# ControlBoard.net
KiCad netlist of a schematic drawn in EAGLE
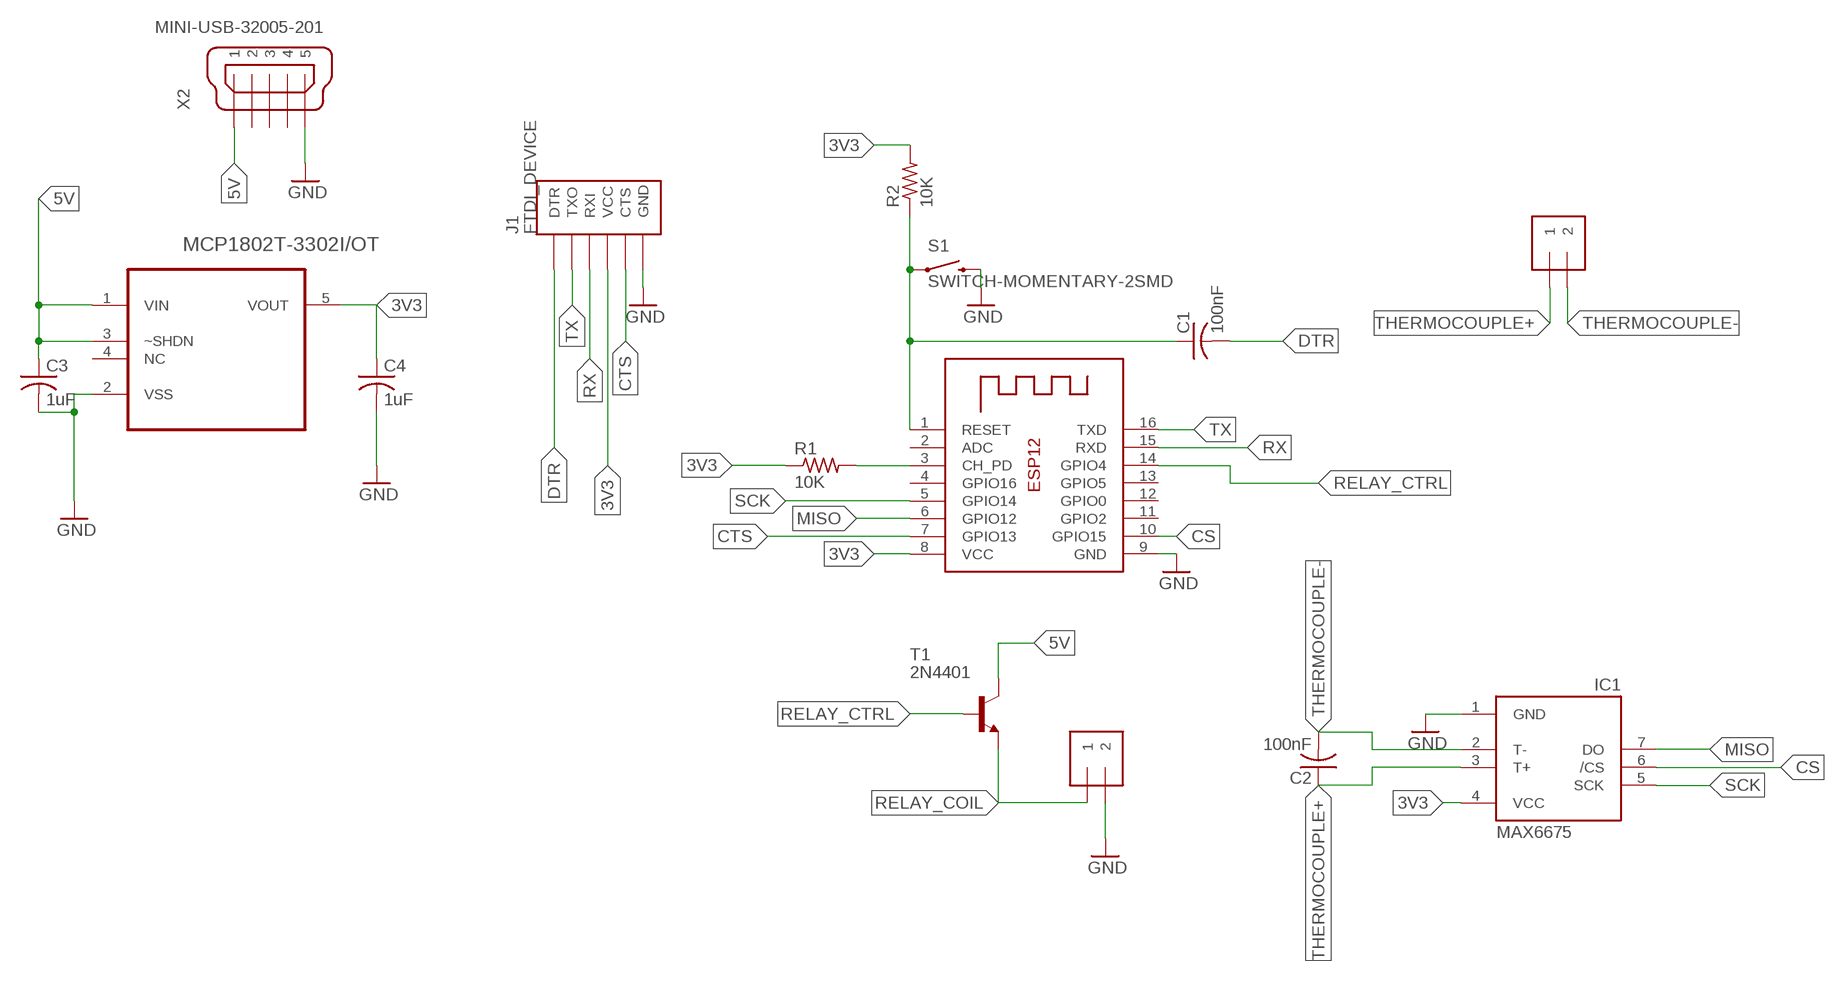
[diagram p0: schematic, sheet 1]

(export (version "E")
  (design (tool "Eeschema 10.0.6"))
  (components
    (comp (ref "C1")
      (value "100nF")
      (footprint "eagle-import:C0603")
      (libsource (lib "eagle-import") (part "C-USC0603"))
    )
    (comp (ref "C2")
      (value "100nF")
      (footprint "eagle-import:C0603")
      (libsource (lib "eagle-import") (part "C-USC0603"))
    )
    (comp (ref "C3")
      (value "1uF")
      (footprint "eagle-import:C0603")
      (libsource (lib "eagle-import") (part "C-USC0603"))
    )
    (comp (ref "C4")
      (value "1uF")
      (footprint "eagle-import:C0603")
      (libsource (lib "eagle-import") (part "C-USC0603"))
    )
    (comp (ref "IC1")
      (value "MAX6675")
      (footprint "eagle-import:SO08")
      (libsource (lib "eagle-import") (part "MAX6675"))
    )
    (comp (ref "J1")
      (value "FTDI_DEVICE")
      (footprint "eagle-import:FTDI_DEVICE_SIDE")
      (libsource (lib "eagle-import") (part "FTDI_DEVICE"))
    )
    (comp (ref "J2")
      (value "1X2-3.5MM")
      (footprint "eagle-import:1X2-3.5MM")
      (libsource (lib "eagle-import") (part "1X2-3.5MM"))
    )
    (comp (ref "J3")
      (value "1X2-3.5MM")
      (footprint "eagle-import:1X2-3.5MM")
      (libsource (lib "eagle-import") (part "1X2-3.5MM"))
    )
    (comp (ref "MCP1802T-3302I/OT")
      (value "MCP1802T-3002I/OT")
      (footprint "eagle-import:SOT95P270X145-5N")
      (libsource (lib "eagle-import") (part "MCP1802T-3002I/OT"))
    )
    (comp (ref "R1")
      (value "10K")
      (footprint "eagle-import:R0603")
      (libsource (lib "eagle-import") (part "R-US_R0603"))
    )
    (comp (ref "R2")
      (value "10K")
      (footprint "eagle-import:R0603")
      (libsource (lib "eagle-import") (part "R-US_R0603"))
    )
    (comp (ref "S1")
      (value "SWITCH-MOMENTARY-2SMD")
      (footprint "eagle-import:TACTILE-SWITCH-SMD")
      (libsource (lib "eagle-import") (part "SWITCH-MOMENTARY-2SMD"))
    )
    (comp (ref "T1")
      (value "2N4401")
      (footprint "eagle-import:TO92-EBC")
      (libsource (lib "eagle-import") (part "-NPN-TO92-EBC"))
    )
    (comp (ref "X1")
      (value "ESP-12")
      (footprint "eagle-import:ESP-12")
      (libsource (lib "eagle-import") (part "ESP-12"))
    )
    (comp (ref "X2")
      (value "MINI-USB-32005-201")
      (footprint "eagle-import:32005-201")
      (libsource (lib "eagle-import") (part "MINI-USB-32005-201"))
    )
  )
  (nets
    (net (code "1") (name "3V3") (class "Default")
      (node (ref "C4") (pin "1") (pinfunction "1_1") (pintype "passive"))
      (node (ref "IC1") (pin "4") (pinfunction "VCC_4") (pintype "power_in"))
      (node (ref "J1") (pin "P$4") (pinfunction "VCC_P$4") (pintype "bidirectional"))
      (node (ref "MCP1802T-3302I/OT") (pin "5") (pinfunction "VOUT_5") (pintype "output"))
      (node (ref "R1") (pin "1") (pinfunction "1_1") (pintype "passive"))
      (node (ref "R2") (pin "2") (pinfunction "2_2") (pintype "passive"))
      (node (ref "X1") (pin "8") (pinfunction "VCC_8") (pintype "power_in"))
    )
    (net (code "2") (name "5V") (class "Default")
      (node (ref "C3") (pin "1") (pinfunction "1_1") (pintype "passive"))
      (node (ref "MCP1802T-3302I/OT") (pin "1") (pinfunction "VIN_1") (pintype "power_in"))
      (node (ref "MCP1802T-3302I/OT") (pin "3") (pinfunction "~{SHDN}_3") (pintype "input"))
      (node (ref "T1") (pin "C") (pinfunction "C_C") (pintype "passive"))
      (node (ref "X2") (pin "1") (pinfunction "1_1") (pintype "passive"))
    )
    (net (code "3") (name "CS") (class "Default")
      (node (ref "IC1") (pin "6") (pinfunction "/CS_6") (pintype "input"))
      (node (ref "X1") (pin "10") (pinfunction "GPIO15_10") (pintype "bidirectional"))
    )
    (net (code "4") (name "CTS") (class "Default")
      (node (ref "J1") (pin "P$5") (pinfunction "CTS_P$5") (pintype "bidirectional"))
      (node (ref "X1") (pin "7") (pinfunction "GPIO13_7") (pintype "bidirectional"))
    )
    (net (code "5") (name "DTR") (class "Default")
      (node (ref "C1") (pin "2") (pinfunction "2_2") (pintype "passive"))
      (node (ref "J1") (pin "P$1") (pinfunction "DTR_P$1") (pintype "bidirectional"))
    )
    (net (code "6") (name "GND") (class "Default")
      (node (ref "C3") (pin "2") (pinfunction "2_2") (pintype "passive"))
      (node (ref "C4") (pin "2") (pinfunction "2_2") (pintype "passive"))
      (node (ref "IC1") (pin "1") (pinfunction "GND_1") (pintype "power_in"))
      (node (ref "J1") (pin "P$6") (pinfunction "GND_P$6") (pintype "bidirectional"))
      (node (ref "J3") (pin "2") (pinfunction "2_2") (pintype "passive"))
      (node (ref "MCP1802T-3302I/OT") (pin "2") (pinfunction "VSS_2") (pintype "passive"))
      (node (ref "S1") (pin "3") (pinfunction "2_3") (pintype "passive"))
      (node (ref "X1") (pin "9") (pinfunction "GND_9") (pintype "power_in"))
      (node (ref "X2") (pin "5") (pinfunction "5_5") (pintype "passive"))
    )
    (net (code "7") (name "MISO") (class "Default")
      (node (ref "IC1") (pin "7") (pinfunction "DO_7") (pintype "output"))
      (node (ref "X1") (pin "6") (pinfunction "GPIO12_6") (pintype "bidirectional"))
    )
    (net (code "8") (name "Net-(X1-CH_PD)") (class "Default")
      (node (ref "R1") (pin "2") (pinfunction "2_2") (pintype "passive"))
      (node (ref "X1") (pin "3") (pinfunction "CH_PD_3") (pintype "input"))
    )
    (net (code "9") (name "Net-(X1-RESET)") (class "Default")
      (node (ref "C1") (pin "1") (pinfunction "1_1") (pintype "passive"))
      (node (ref "R2") (pin "1") (pinfunction "1_1") (pintype "passive"))
      (node (ref "S1") (pin "1") (pinfunction "1_1") (pintype "passive"))
      (node (ref "X1") (pin "1") (pinfunction "RESET_1") (pintype "input"))
    )
    (net (code "10") (name "RELAY_COIL") (class "Default")
      (node (ref "J3") (pin "1") (pinfunction "1_1") (pintype "passive"))
      (node (ref "T1") (pin "E") (pinfunction "E_E") (pintype "passive"))
    )
    (net (code "11") (name "RELAY_CTRL") (class "Default")
      (node (ref "T1") (pin "B") (pinfunction "B_B") (pintype "passive"))
      (node (ref "X1") (pin "14") (pinfunction "GPIO4_14") (pintype "bidirectional"))
    )
    (net (code "12") (name "RX") (class "Default")
      (node (ref "J1") (pin "P$3") (pinfunction "RXI_P$3") (pintype "bidirectional"))
      (node (ref "X1") (pin "15") (pinfunction "RXD_15") (pintype "input"))
    )
    (net (code "13") (name "SCK") (class "Default")
      (node (ref "IC1") (pin "5") (pinfunction "SCK_5") (pintype "input"))
      (node (ref "X1") (pin "5") (pinfunction "GPIO14_5") (pintype "bidirectional"))
    )
    (net (code "14") (name "THERMOCOUPLE+") (class "Default")
      (node (ref "C2") (pin "1") (pinfunction "1_1") (pintype "passive"))
      (node (ref "IC1") (pin "3") (pinfunction "T+_3") (pintype "input"))
      (node (ref "J2") (pin "1") (pinfunction "1_1") (pintype "passive"))
    )
    (net (code "15") (name "THERMOCOUPLE-") (class "Default")
      (node (ref "C2") (pin "2") (pinfunction "2_2") (pintype "passive"))
      (node (ref "IC1") (pin "2") (pinfunction "T-_2") (pintype "input"))
      (node (ref "J2") (pin "2") (pinfunction "2_2") (pintype "passive"))
    )
    (net (code "16") (name "TX") (class "Default")
      (node (ref "J1") (pin "P$2") (pinfunction "TXO_P$2") (pintype "bidirectional"))
      (node (ref "X1") (pin "16") (pinfunction "TXD_16") (pintype "output"))
    )
    (net (code "17") (name "unconnected-(MCP1802T-3302I/OT-NC-Pad4)") (class "Default")
      (node (ref "MCP1802T-3302I/OT") (pin "4") (pinfunction "NC_4") (pintype "no_connect"))
    )
    (net (code "18") (name "unconnected-(X1-ADC-Pad2)") (class "Default")
      (node (ref "X1") (pin "2") (pinfunction "ADC_2") (pintype "passive"))
    )
    (net (code "19") (name "unconnected-(X1-GPIO0-Pad12)") (class "Default")
      (node (ref "X1") (pin "12") (pinfunction "GPIO0_12") (pintype "bidirectional"))
    )
    (net (code "20") (name "unconnected-(X1-GPIO2-Pad11)") (class "Default")
      (node (ref "X1") (pin "11") (pinfunction "GPIO2_11") (pintype "bidirectional"))
    )
    (net (code "21") (name "unconnected-(X1-GPIO5-Pad13)") (class "Default")
      (node (ref "X1") (pin "13") (pinfunction "GPIO5_13") (pintype "bidirectional"))
    )
    (net (code "22") (name "unconnected-(X1-GPIO16-Pad4)") (class "Default")
      (node (ref "X1") (pin "4") (pinfunction "GPIO16_4") (pintype "bidirectional"))
    )
    (net (code "23") (name "unconnected-(X2-Pad2)") (class "Default")
      (node (ref "X2") (pin "2") (pinfunction "2_2") (pintype "passive"))
    )
    (net (code "24") (name "unconnected-(X2-Pad3)") (class "Default")
      (node (ref "X2") (pin "3") (pinfunction "3_3") (pintype "passive"))
    )
    (net (code "25") (name "unconnected-(X2-Pad4)") (class "Default")
      (node (ref "X2") (pin "4") (pinfunction "4_4") (pintype "passive"))
    )
  )
)
